# shift_register.net
KiCad netlist of a schematic drawn in EAGLE
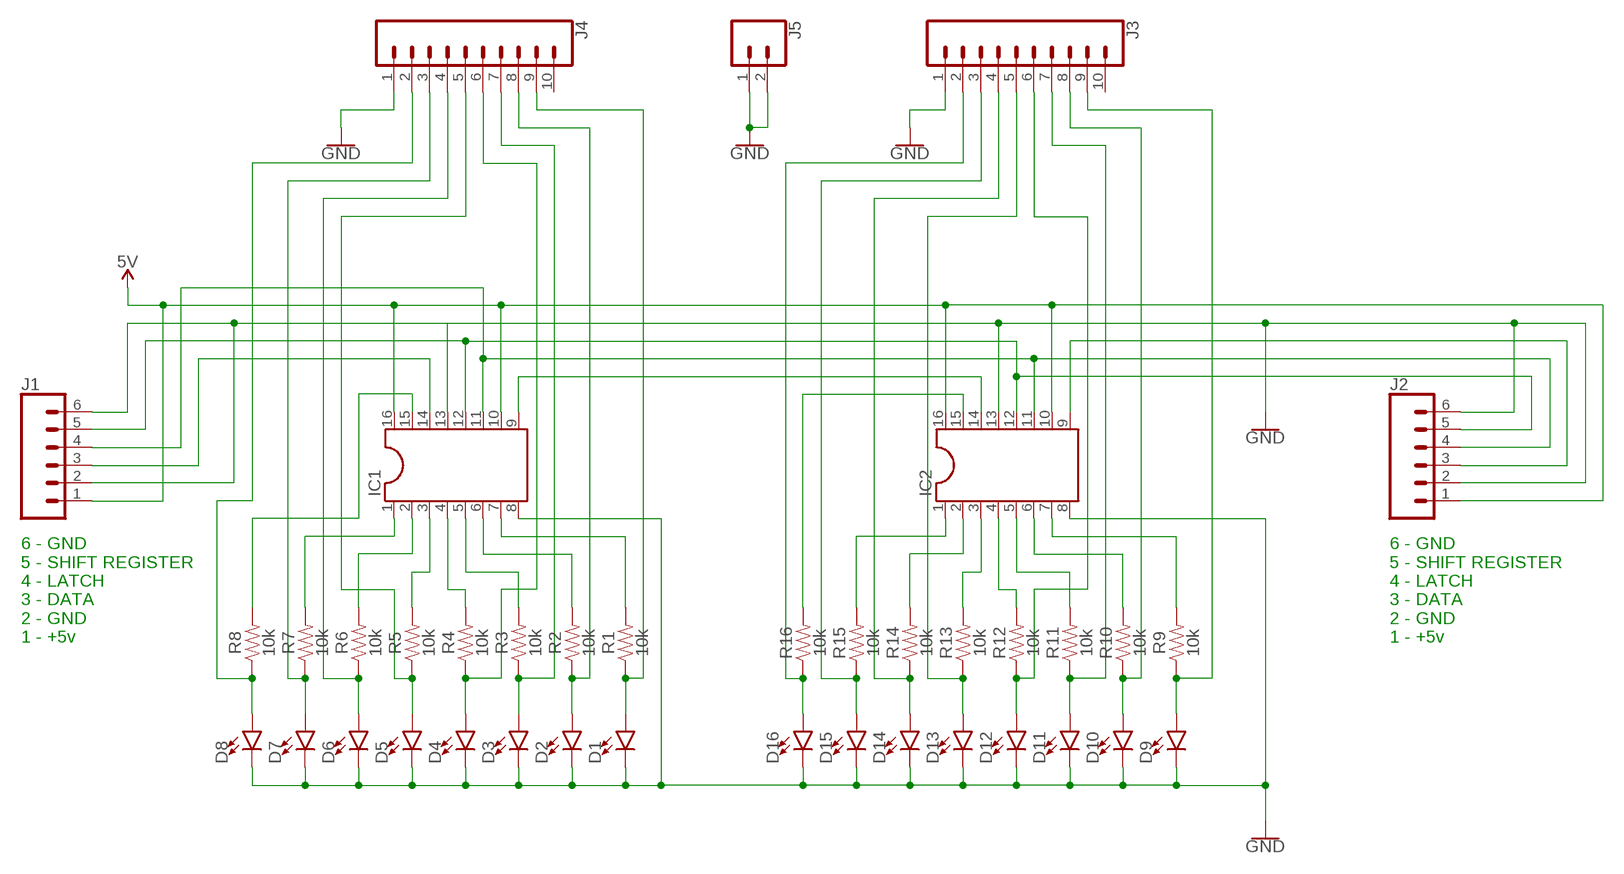
[diagram p0: schematic, sheet 1]

(export (version "E")
  (design (tool "Eeschema 10.0.6"))
  (components
    (comp (ref "D1")
      (value "LED3MM")
      (footprint "eagle-import:LED_3MM")
      (libsource (lib "eagle-import") (part "LED3MM"))
    )
    (comp (ref "D2")
      (value "LED3MM")
      (footprint "eagle-import:LED_3MM")
      (libsource (lib "eagle-import") (part "LED3MM"))
    )
    (comp (ref "D3")
      (value "LED3MM")
      (footprint "eagle-import:LED_3MM")
      (libsource (lib "eagle-import") (part "LED3MM"))
    )
    (comp (ref "D4")
      (value "LED3MM")
      (footprint "eagle-import:LED_3MM")
      (libsource (lib "eagle-import") (part "LED3MM"))
    )
    (comp (ref "D5")
      (value "LED3MM")
      (footprint "eagle-import:LED_3MM")
      (libsource (lib "eagle-import") (part "LED3MM"))
    )
    (comp (ref "D6")
      (value "LED3MM")
      (footprint "eagle-import:LED_3MM")
      (libsource (lib "eagle-import") (part "LED3MM"))
    )
    (comp (ref "D7")
      (value "LED3MM")
      (footprint "eagle-import:LED_3MM")
      (libsource (lib "eagle-import") (part "LED3MM"))
    )
    (comp (ref "D8")
      (value "LED3MM")
      (footprint "eagle-import:LED_3MM")
      (libsource (lib "eagle-import") (part "LED3MM"))
    )
    (comp (ref "D9")
      (value "LED3MM")
      (footprint "eagle-import:LED_3MM")
      (libsource (lib "eagle-import") (part "LED3MM"))
    )
    (comp (ref "D10")
      (value "LED3MM")
      (footprint "eagle-import:LED_3MM")
      (libsource (lib "eagle-import") (part "LED3MM"))
    )
    (comp (ref "D11")
      (value "LED3MM")
      (footprint "eagle-import:LED_3MM")
      (libsource (lib "eagle-import") (part "LED3MM"))
    )
    (comp (ref "D12")
      (value "LED3MM")
      (footprint "eagle-import:LED_3MM")
      (libsource (lib "eagle-import") (part "LED3MM"))
    )
    (comp (ref "D13")
      (value "LED3MM")
      (footprint "eagle-import:LED_3MM")
      (libsource (lib "eagle-import") (part "LED3MM"))
    )
    (comp (ref "D14")
      (value "LED3MM")
      (footprint "eagle-import:LED_3MM")
      (libsource (lib "eagle-import") (part "LED3MM"))
    )
    (comp (ref "D15")
      (value "LED3MM")
      (footprint "eagle-import:LED_3MM")
      (libsource (lib "eagle-import") (part "LED3MM"))
    )
    (comp (ref "D16")
      (value "LED3MM")
      (footprint "eagle-import:LED_3MM")
      (libsource (lib "eagle-import") (part "LED3MM"))
    )
    (comp (ref "IC1")
      (value "DIL16")
      (footprint "eagle-import:DIL16")
      (libsource (lib "eagle-import") (part "DIL16"))
    )
    (comp (ref "IC2")
      (value "DIL16")
      (footprint "eagle-import:DIL16")
      (libsource (lib "eagle-import") (part "DIL16"))
    )
    (comp (ref "J1")
      (value "CONN_06SILK_FEMALE_PTH")
      (footprint "eagle-import:1X06")
      (libsource (lib "eagle-import") (part "CONN_06SILK_FEMALE_PTH"))
    )
    (comp (ref "J2")
      (value "CONN_06SILK_FEMALE_PTH")
      (footprint "eagle-import:1X06")
      (libsource (lib "eagle-import") (part "CONN_06SILK_FEMALE_PTH"))
    )
    (comp (ref "J3")
      (value "CONN_10\"")
      (footprint "eagle-import:1X10")
      (libsource (lib "eagle-import") (part "CONN_10{dblquote}"))
    )
    (comp (ref "J4")
      (value "CONN_10\"")
      (footprint "eagle-import:1X10")
      (libsource (lib "eagle-import") (part "CONN_10{dblquote}"))
    )
    (comp (ref "J5")
      (value "CONN_02")
      (footprint "eagle-import:1X02")
      (libsource (lib "eagle-import") (part "CONN_02"))
    )
    (comp (ref "R1")
      (value "10k")
      (footprint "eagle-import:AXIAL-0.3")
      (libsource (lib "eagle-import") (part "10KOHM-HORIZ-1/6W-5%"))
    )
    (comp (ref "R2")
      (value "10k")
      (footprint "eagle-import:AXIAL-0.3")
      (libsource (lib "eagle-import") (part "10KOHM-HORIZ-1/6W-5%"))
    )
    (comp (ref "R3")
      (value "10k")
      (footprint "eagle-import:AXIAL-0.3")
      (libsource (lib "eagle-import") (part "10KOHM-HORIZ-1/6W-5%"))
    )
    (comp (ref "R4")
      (value "10k")
      (footprint "eagle-import:AXIAL-0.3")
      (libsource (lib "eagle-import") (part "10KOHM-HORIZ-1/6W-5%"))
    )
    (comp (ref "R5")
      (value "10k")
      (footprint "eagle-import:AXIAL-0.3")
      (libsource (lib "eagle-import") (part "10KOHM-HORIZ-1/6W-5%"))
    )
    (comp (ref "R6")
      (value "10k")
      (footprint "eagle-import:AXIAL-0.3")
      (libsource (lib "eagle-import") (part "10KOHM-HORIZ-1/6W-5%"))
    )
    (comp (ref "R7")
      (value "10k")
      (footprint "eagle-import:AXIAL-0.3")
      (libsource (lib "eagle-import") (part "10KOHM-HORIZ-1/6W-5%"))
    )
    (comp (ref "R8")
      (value "10k")
      (footprint "eagle-import:AXIAL-0.3")
      (libsource (lib "eagle-import") (part "10KOHM-HORIZ-1/6W-5%"))
    )
    (comp (ref "R9")
      (value "10k")
      (footprint "eagle-import:AXIAL-0.3")
      (libsource (lib "eagle-import") (part "10KOHM-HORIZ-1/6W-5%"))
    )
    (comp (ref "R10")
      (value "10k")
      (footprint "eagle-import:AXIAL-0.3")
      (libsource (lib "eagle-import") (part "10KOHM-HORIZ-1/6W-5%"))
    )
    (comp (ref "R11")
      (value "10k")
      (footprint "eagle-import:AXIAL-0.3")
      (libsource (lib "eagle-import") (part "10KOHM-HORIZ-1/6W-5%"))
    )
    (comp (ref "R12")
      (value "10k")
      (footprint "eagle-import:AXIAL-0.3")
      (libsource (lib "eagle-import") (part "10KOHM-HORIZ-1/6W-5%"))
    )
    (comp (ref "R13")
      (value "10k")
      (footprint "eagle-import:AXIAL-0.3")
      (libsource (lib "eagle-import") (part "10KOHM-HORIZ-1/6W-5%"))
    )
    (comp (ref "R14")
      (value "10k")
      (footprint "eagle-import:AXIAL-0.3")
      (libsource (lib "eagle-import") (part "10KOHM-HORIZ-1/6W-5%"))
    )
    (comp (ref "R15")
      (value "10k")
      (footprint "eagle-import:AXIAL-0.3")
      (libsource (lib "eagle-import") (part "10KOHM-HORIZ-1/6W-5%"))
    )
    (comp (ref "R16")
      (value "10k")
      (footprint "eagle-import:AXIAL-0.3")
      (libsource (lib "eagle-import") (part "10KOHM-HORIZ-1/6W-5%"))
    )
  )
  (nets
    (net (code "1") (name "5V") (class "Default")
      (node (ref "IC1") (pin "10") (pinfunction "10_10") (pintype "passive"))
      (node (ref "IC1") (pin "16") (pinfunction "16_16") (pintype "passive"))
      (node (ref "IC2") (pin "10") (pinfunction "10_10") (pintype "passive"))
      (node (ref "IC2") (pin "16") (pinfunction "16_16") (pintype "passive"))
      (node (ref "J1") (pin "1") (pinfunction "1_1") (pintype "passive"))
      (node (ref "J2") (pin "1") (pinfunction "1_1") (pintype "passive"))
    )
    (net (code "2") (name "GND") (class "Default")
      (node (ref "D1") (pin "K") (pinfunction "C_K") (pintype "passive"))
      (node (ref "D10") (pin "K") (pinfunction "C_K") (pintype "passive"))
      (node (ref "D11") (pin "K") (pinfunction "C_K") (pintype "passive"))
      (node (ref "D12") (pin "K") (pinfunction "C_K") (pintype "passive"))
      (node (ref "D13") (pin "K") (pinfunction "C_K") (pintype "passive"))
      (node (ref "D14") (pin "K") (pinfunction "C_K") (pintype "passive"))
      (node (ref "D15") (pin "K") (pinfunction "C_K") (pintype "passive"))
      (node (ref "D16") (pin "K") (pinfunction "C_K") (pintype "passive"))
      (node (ref "D2") (pin "K") (pinfunction "C_K") (pintype "passive"))
      (node (ref "D3") (pin "K") (pinfunction "C_K") (pintype "passive"))
      (node (ref "D4") (pin "K") (pinfunction "C_K") (pintype "passive"))
      (node (ref "D5") (pin "K") (pinfunction "C_K") (pintype "passive"))
      (node (ref "D6") (pin "K") (pinfunction "C_K") (pintype "passive"))
      (node (ref "D7") (pin "K") (pinfunction "C_K") (pintype "passive"))
      (node (ref "D8") (pin "K") (pinfunction "C_K") (pintype "passive"))
      (node (ref "D9") (pin "K") (pinfunction "C_K") (pintype "passive"))
      (node (ref "IC1") (pin "13") (pinfunction "13_13") (pintype "passive"))
      (node (ref "IC1") (pin "8") (pinfunction "8_8") (pintype "passive"))
      (node (ref "IC2") (pin "13") (pinfunction "13_13") (pintype "passive"))
      (node (ref "IC2") (pin "8") (pinfunction "8_8") (pintype "passive"))
      (node (ref "J1") (pin "2") (pinfunction "2_2") (pintype "passive"))
      (node (ref "J1") (pin "6") (pinfunction "6_6") (pintype "passive"))
      (node (ref "J2") (pin "2") (pinfunction "2_2") (pintype "passive"))
      (node (ref "J2") (pin "6") (pinfunction "6_6") (pintype "passive"))
      (node (ref "J3") (pin "1") (pinfunction "1_1") (pintype "passive"))
      (node (ref "J4") (pin "1") (pinfunction "1_1") (pintype "passive"))
      (node (ref "J5") (pin "1") (pinfunction "1_1") (pintype "passive"))
      (node (ref "J5") (pin "2") (pinfunction "2_2") (pintype "passive"))
    )
    (net (code "3") (name "Net-(IC1-Pad9)") (class "Default")
      (node (ref "IC1") (pin "9") (pinfunction "9_9") (pintype "passive"))
      (node (ref "IC2") (pin "14") (pinfunction "14_14") (pintype "passive"))
    )
    (net (code "4") (name "Net-(IC1-Pad11)") (class "Default")
      (node (ref "IC1") (pin "11") (pinfunction "11_11") (pintype "passive"))
      (node (ref "IC2") (pin "11") (pinfunction "11_11") (pintype "passive"))
      (node (ref "J1") (pin "4") (pinfunction "4_4") (pintype "passive"))
      (node (ref "J2") (pin "4") (pinfunction "4_4") (pintype "passive"))
    )
    (net (code "5") (name "Net-(IC1-Pad12)") (class "Default")
      (node (ref "IC1") (pin "12") (pinfunction "12_12") (pintype "passive"))
      (node (ref "IC2") (pin "12") (pinfunction "12_12") (pintype "passive"))
      (node (ref "J1") (pin "5") (pinfunction "5_5") (pintype "passive"))
      (node (ref "J2") (pin "5") (pinfunction "5_5") (pintype "passive"))
    )
    (net (code "6") (name "Net-(IC1-Pad14)") (class "Default")
      (node (ref "IC1") (pin "14") (pinfunction "14_14") (pintype "passive"))
      (node (ref "J1") (pin "3") (pinfunction "3_3") (pintype "passive"))
    )
    (net (code "7") (name "Net-(IC2-Pad9)") (class "Default")
      (node (ref "IC2") (pin "9") (pinfunction "9_9") (pintype "passive"))
      (node (ref "J2") (pin "3") (pinfunction "3_3") (pintype "passive"))
    )
    (net (code "8") (name "Net-(R1-1)") (class "Default")
      (node (ref "D1") (pin "A") (pinfunction "A_A") (pintype "passive"))
      (node (ref "J4") (pin "9") (pinfunction "9_9") (pintype "passive"))
      (node (ref "R1") (pin "P$1") (pinfunction "1_P$1") (pintype "passive"))
    )
    (net (code "9") (name "Net-(R1-2)") (class "Default")
      (node (ref "IC1") (pin "7") (pinfunction "7_7") (pintype "passive"))
      (node (ref "R1") (pin "P$2") (pinfunction "2_P$2") (pintype "passive"))
    )
    (net (code "10") (name "Net-(R2-1)") (class "Default")
      (node (ref "D2") (pin "A") (pinfunction "A_A") (pintype "passive"))
      (node (ref "J4") (pin "8") (pinfunction "8_8") (pintype "passive"))
      (node (ref "R2") (pin "P$1") (pinfunction "1_P$1") (pintype "passive"))
    )
    (net (code "11") (name "Net-(R2-2)") (class "Default")
      (node (ref "IC1") (pin "6") (pinfunction "6_6") (pintype "passive"))
      (node (ref "R2") (pin "P$2") (pinfunction "2_P$2") (pintype "passive"))
    )
    (net (code "12") (name "Net-(R3-1)") (class "Default")
      (node (ref "D3") (pin "A") (pinfunction "A_A") (pintype "passive"))
      (node (ref "J4") (pin "7") (pinfunction "7_7") (pintype "passive"))
      (node (ref "R3") (pin "P$1") (pinfunction "1_P$1") (pintype "passive"))
    )
    (net (code "13") (name "Net-(R3-2)") (class "Default")
      (node (ref "IC1") (pin "5") (pinfunction "5_5") (pintype "passive"))
      (node (ref "R3") (pin "P$2") (pinfunction "2_P$2") (pintype "passive"))
    )
    (net (code "14") (name "Net-(R4-1)") (class "Default")
      (node (ref "D4") (pin "A") (pinfunction "A_A") (pintype "passive"))
      (node (ref "J4") (pin "6") (pinfunction "6_6") (pintype "passive"))
      (node (ref "R4") (pin "P$1") (pinfunction "1_P$1") (pintype "passive"))
    )
    (net (code "15") (name "Net-(R4-2)") (class "Default")
      (node (ref "IC1") (pin "4") (pinfunction "4_4") (pintype "passive"))
      (node (ref "R4") (pin "P$2") (pinfunction "2_P$2") (pintype "passive"))
    )
    (net (code "16") (name "Net-(R5-1)") (class "Default")
      (node (ref "D5") (pin "A") (pinfunction "A_A") (pintype "passive"))
      (node (ref "J4") (pin "5") (pinfunction "5_5") (pintype "passive"))
      (node (ref "R5") (pin "P$1") (pinfunction "1_P$1") (pintype "passive"))
    )
    (net (code "17") (name "Net-(R5-2)") (class "Default")
      (node (ref "IC1") (pin "3") (pinfunction "3_3") (pintype "passive"))
      (node (ref "R5") (pin "P$2") (pinfunction "2_P$2") (pintype "passive"))
    )
    (net (code "18") (name "Net-(R6-1)") (class "Default")
      (node (ref "D6") (pin "A") (pinfunction "A_A") (pintype "passive"))
      (node (ref "J4") (pin "4") (pinfunction "4_4") (pintype "passive"))
      (node (ref "R6") (pin "P$1") (pinfunction "1_P$1") (pintype "passive"))
    )
    (net (code "19") (name "Net-(R6-2)") (class "Default")
      (node (ref "IC1") (pin "2") (pinfunction "2_2") (pintype "passive"))
      (node (ref "R6") (pin "P$2") (pinfunction "2_P$2") (pintype "passive"))
    )
    (net (code "20") (name "Net-(R7-1)") (class "Default")
      (node (ref "D7") (pin "A") (pinfunction "A_A") (pintype "passive"))
      (node (ref "J4") (pin "3") (pinfunction "3_3") (pintype "passive"))
      (node (ref "R7") (pin "P$1") (pinfunction "1_P$1") (pintype "passive"))
    )
    (net (code "21") (name "Net-(R7-2)") (class "Default")
      (node (ref "IC1") (pin "1") (pinfunction "1_1") (pintype "passive"))
      (node (ref "R7") (pin "P$2") (pinfunction "2_P$2") (pintype "passive"))
    )
    (net (code "22") (name "Net-(R8-1)") (class "Default")
      (node (ref "D8") (pin "A") (pinfunction "A_A") (pintype "passive"))
      (node (ref "J4") (pin "2") (pinfunction "2_2") (pintype "passive"))
      (node (ref "R8") (pin "P$1") (pinfunction "1_P$1") (pintype "passive"))
    )
    (net (code "23") (name "Net-(R8-2)") (class "Default")
      (node (ref "IC1") (pin "15") (pinfunction "15_15") (pintype "passive"))
      (node (ref "R8") (pin "P$2") (pinfunction "2_P$2") (pintype "passive"))
    )
    (net (code "24") (name "Net-(R9-1)") (class "Default")
      (node (ref "D9") (pin "A") (pinfunction "A_A") (pintype "passive"))
      (node (ref "J3") (pin "9") (pinfunction "9_9") (pintype "passive"))
      (node (ref "R9") (pin "P$1") (pinfunction "1_P$1") (pintype "passive"))
    )
    (net (code "25") (name "Net-(R9-2)") (class "Default")
      (node (ref "IC2") (pin "7") (pinfunction "7_7") (pintype "passive"))
      (node (ref "R9") (pin "P$2") (pinfunction "2_P$2") (pintype "passive"))
    )
    (net (code "26") (name "Net-(R10-1)") (class "Default")
      (node (ref "D10") (pin "A") (pinfunction "A_A") (pintype "passive"))
      (node (ref "J3") (pin "8") (pinfunction "8_8") (pintype "passive"))
      (node (ref "R10") (pin "P$1") (pinfunction "1_P$1") (pintype "passive"))
    )
    (net (code "27") (name "Net-(R10-2)") (class "Default")
      (node (ref "IC2") (pin "6") (pinfunction "6_6") (pintype "passive"))
      (node (ref "R10") (pin "P$2") (pinfunction "2_P$2") (pintype "passive"))
    )
    (net (code "28") (name "Net-(R11-1)") (class "Default")
      (node (ref "D11") (pin "A") (pinfunction "A_A") (pintype "passive"))
      (node (ref "J3") (pin "7") (pinfunction "7_7") (pintype "passive"))
      (node (ref "R11") (pin "P$1") (pinfunction "1_P$1") (pintype "passive"))
    )
    (net (code "29") (name "Net-(R11-2)") (class "Default")
      (node (ref "IC2") (pin "5") (pinfunction "5_5") (pintype "passive"))
      (node (ref "R11") (pin "P$2") (pinfunction "2_P$2") (pintype "passive"))
    )
    (net (code "30") (name "Net-(R12-1)") (class "Default")
      (node (ref "D12") (pin "A") (pinfunction "A_A") (pintype "passive"))
      (node (ref "J3") (pin "6") (pinfunction "6_6") (pintype "passive"))
      (node (ref "R12") (pin "P$1") (pinfunction "1_P$1") (pintype "passive"))
    )
    (net (code "31") (name "Net-(R12-2)") (class "Default")
      (node (ref "IC2") (pin "4") (pinfunction "4_4") (pintype "passive"))
      (node (ref "R12") (pin "P$2") (pinfunction "2_P$2") (pintype "passive"))
    )
    (net (code "32") (name "Net-(R13-1)") (class "Default")
      (node (ref "D13") (pin "A") (pinfunction "A_A") (pintype "passive"))
      (node (ref "J3") (pin "5") (pinfunction "5_5") (pintype "passive"))
      (node (ref "R13") (pin "P$1") (pinfunction "1_P$1") (pintype "passive"))
    )
    (net (code "33") (name "Net-(R13-2)") (class "Default")
      (node (ref "IC2") (pin "3") (pinfunction "3_3") (pintype "passive"))
      (node (ref "R13") (pin "P$2") (pinfunction "2_P$2") (pintype "passive"))
    )
    (net (code "34") (name "Net-(R14-1)") (class "Default")
      (node (ref "D14") (pin "A") (pinfunction "A_A") (pintype "passive"))
      (node (ref "J3") (pin "4") (pinfunction "4_4") (pintype "passive"))
      (node (ref "R14") (pin "P$1") (pinfunction "1_P$1") (pintype "passive"))
    )
    (net (code "35") (name "Net-(R14-2)") (class "Default")
      (node (ref "IC2") (pin "2") (pinfunction "2_2") (pintype "passive"))
      (node (ref "R14") (pin "P$2") (pinfunction "2_P$2") (pintype "passive"))
    )
    (net (code "36") (name "Net-(R15-1)") (class "Default")
      (node (ref "D15") (pin "A") (pinfunction "A_A") (pintype "passive"))
      (node (ref "J3") (pin "3") (pinfunction "3_3") (pintype "passive"))
      (node (ref "R15") (pin "P$1") (pinfunction "1_P$1") (pintype "passive"))
    )
    (net (code "37") (name "Net-(R15-2)") (class "Default")
      (node (ref "IC2") (pin "1") (pinfunction "1_1") (pintype "passive"))
      (node (ref "R15") (pin "P$2") (pinfunction "2_P$2") (pintype "passive"))
    )
    (net (code "38") (name "Net-(R16-1)") (class "Default")
      (node (ref "D16") (pin "A") (pinfunction "A_A") (pintype "passive"))
      (node (ref "J3") (pin "2") (pinfunction "2_2") (pintype "passive"))
      (node (ref "R16") (pin "P$1") (pinfunction "1_P$1") (pintype "passive"))
    )
    (net (code "39") (name "Net-(R16-2)") (class "Default")
      (node (ref "IC2") (pin "15") (pinfunction "15_15") (pintype "passive"))
      (node (ref "R16") (pin "P$2") (pinfunction "2_P$2") (pintype "passive"))
    )
    (net (code "40") (name "unconnected-(J3-Pad10)") (class "Default")
      (node (ref "J3") (pin "10") (pinfunction "10_10") (pintype "passive"))
    )
    (net (code "41") (name "unconnected-(J4-Pad10)") (class "Default")
      (node (ref "J4") (pin "10") (pinfunction "10_10") (pintype "passive"))
    )
  )
)
